# Conversor_R04.net
KiCad netlist of a schematic drawn in EAGLE
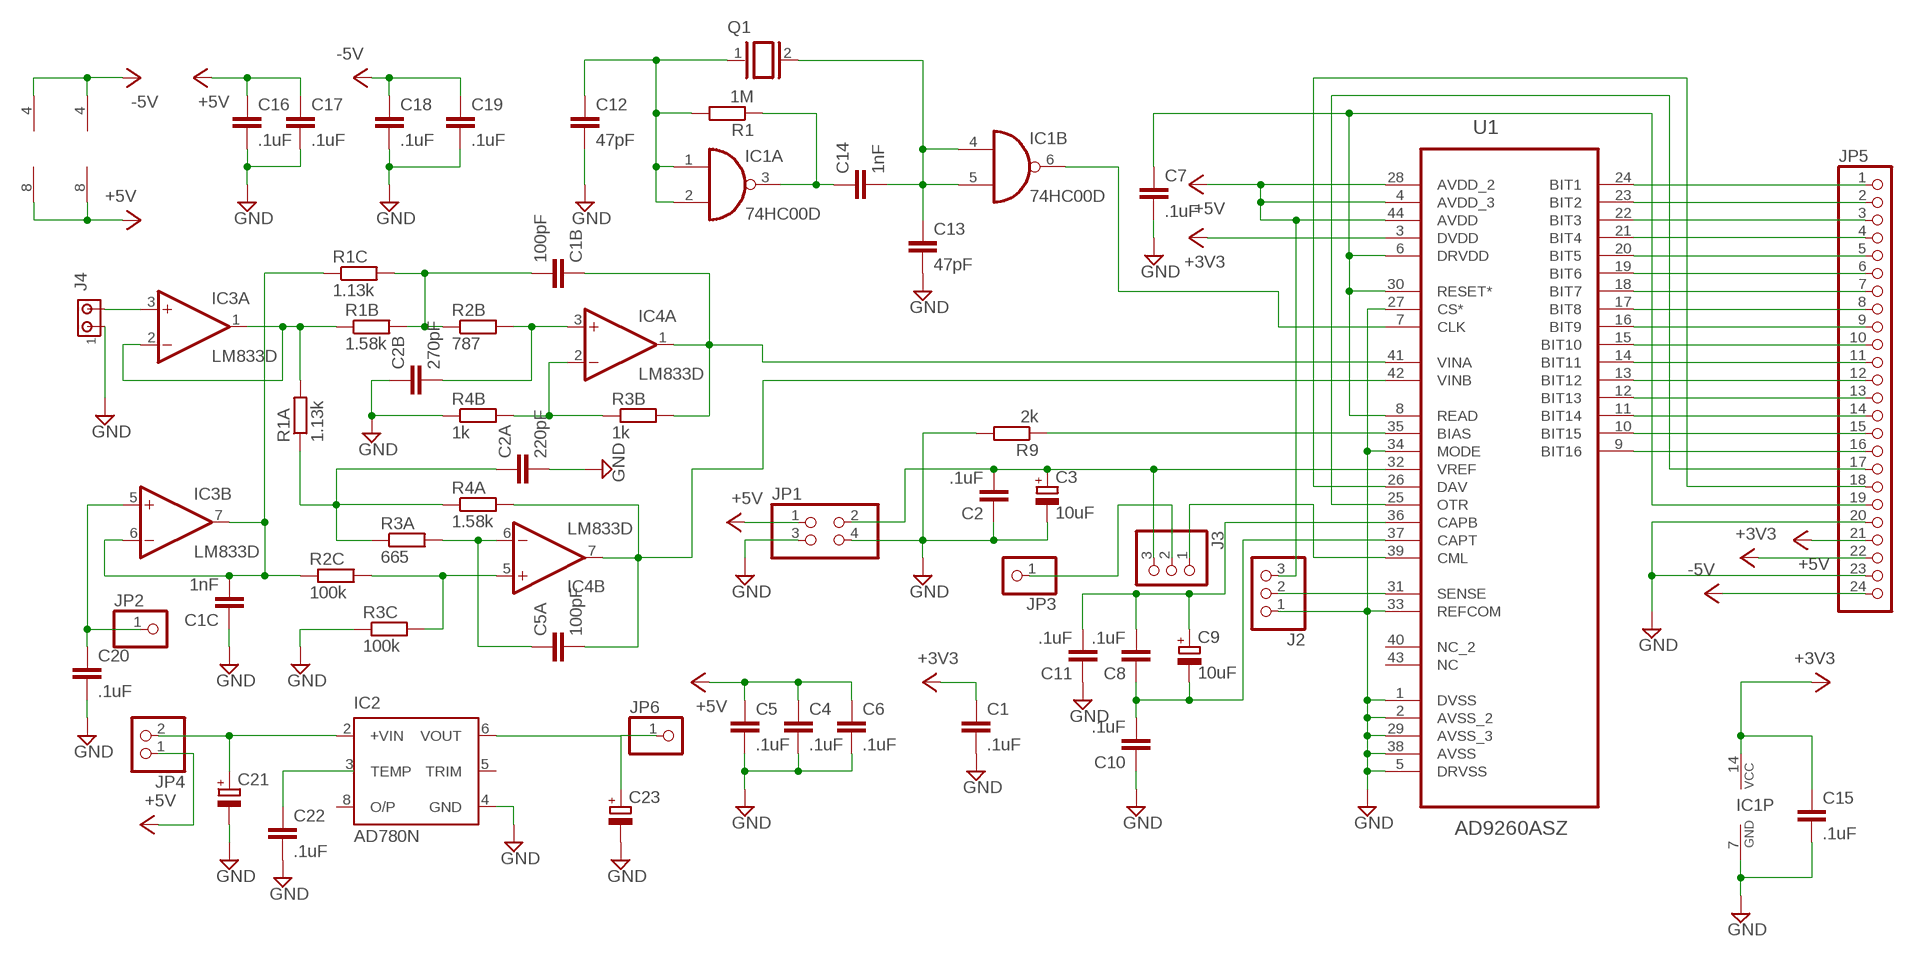
[diagram p0: schematic, sheet 1]

(export (version "E")
  (design (tool "Eeschema 10.0.6"))
  (components
    (comp (ref "C1")
      (value ".1uF")
      (footprint "eagle-import:C050-024X044")
      (libsource (lib "eagle-import") (part "C-EU050-024X044"))
    )
    (comp (ref "C1B")
      (value "100pF")
      (footprint "eagle-import:C025-024X044")
      (libsource (lib "eagle-import") (part "C-EU025-024X044"))
    )
    (comp (ref "C1C")
      (value "1nF")
      (footprint "eagle-import:C025-024X044")
      (libsource (lib "eagle-import") (part "C-EU025-024X044"))
    )
    (comp (ref "C2")
      (value ".1uF")
      (footprint "eagle-import:C050-024X044")
      (libsource (lib "eagle-import") (part "C-EU050-024X044"))
    )
    (comp (ref "C2A")
      (value "220pF")
      (footprint "eagle-import:C050-024X044")
      (libsource (lib "eagle-import") (part "C-EU050-024X044"))
    )
    (comp (ref "C2B")
      (value "270pF")
      (footprint "eagle-import:C025-024X044")
      (libsource (lib "eagle-import") (part "C-EU025-024X044"))
    )
    (comp (ref "C3")
      (value "10uF")
      (footprint "eagle-import:E2-5")
      (libsource (lib "eagle-import") (part "CPOL-EUE2-5"))
    )
    (comp (ref "C4")
      (value ".1uF")
      (footprint "eagle-import:C050-024X044")
      (libsource (lib "eagle-import") (part "C-EU050-024X044"))
    )
    (comp (ref "C5")
      (value ".1uF")
      (footprint "eagle-import:C050-024X044")
      (libsource (lib "eagle-import") (part "C-EU050-024X044"))
    )
    (comp (ref "C5A")
      (value "100pF")
      (footprint "eagle-import:C025-024X044")
      (libsource (lib "eagle-import") (part "C-EU025-024X044"))
    )
    (comp (ref "C6")
      (value ".1uF")
      (footprint "eagle-import:C050-024X044")
      (libsource (lib "eagle-import") (part "C-EU050-024X044"))
    )
    (comp (ref "C7")
      (value ".1uF")
      (footprint "eagle-import:C050-024X044")
      (libsource (lib "eagle-import") (part "C-EU050-024X044"))
    )
    (comp (ref "C8")
      (value ".1uF")
      (footprint "eagle-import:C050-024X044")
      (libsource (lib "eagle-import") (part "C-EU050-024X044"))
    )
    (comp (ref "C9")
      (value "10uF")
      (footprint "eagle-import:E2-5")
      (libsource (lib "eagle-import") (part "CPOL-EUE2-5"))
    )
    (comp (ref "C10")
      (value ".1uF")
      (footprint "eagle-import:C050-024X044")
      (libsource (lib "eagle-import") (part "C-EU050-024X044"))
    )
    (comp (ref "C11")
      (value ".1uF")
      (footprint "eagle-import:C050-024X044")
      (libsource (lib "eagle-import") (part "C-EU050-024X044"))
    )
    (comp (ref "C12")
      (value "47pF")
      (footprint "eagle-import:C025-024X044")
      (libsource (lib "eagle-import") (part "C-EU025-024X044"))
    )
    (comp (ref "C13")
      (value "47pF")
      (footprint "eagle-import:C025-024X044")
      (libsource (lib "eagle-import") (part "C-EU025-024X044"))
    )
    (comp (ref "C14")
      (value "1nF")
      (footprint "eagle-import:C025-024X044")
      (libsource (lib "eagle-import") (part "C-EU025-024X044"))
    )
    (comp (ref "C15")
      (value ".1uF")
      (footprint "eagle-import:C050-024X044")
      (libsource (lib "eagle-import") (part "C-EU050-024X044"))
    )
    (comp (ref "C16")
      (value ".1uF")
      (footprint "eagle-import:C050-024X044")
      (libsource (lib "eagle-import") (part "C-EU050-024X044"))
    )
    (comp (ref "C17")
      (value ".1uF")
      (footprint "eagle-import:C050-024X044")
      (libsource (lib "eagle-import") (part "C-EU050-024X044"))
    )
    (comp (ref "C18")
      (value ".1uF")
      (footprint "eagle-import:C050-024X044")
      (libsource (lib "eagle-import") (part "C-EU050-024X044"))
    )
    (comp (ref "C19")
      (value ".1uF")
      (footprint "eagle-import:C050-024X044")
      (libsource (lib "eagle-import") (part "C-EU050-024X044"))
    )
    (comp (ref "C20")
      (value ".1uF")
      (footprint "eagle-import:C050-024X044")
      (libsource (lib "eagle-import") (part "C-EU050-024X044"))
    )
    (comp (ref "C21")
      (value "CPOL-EUE2,5-6E")
      (footprint "eagle-import:E2,5-6E")
      (libsource (lib "eagle-import") (part "CPOL-EUE2,5-6E"))
    )
    (comp (ref "C22")
      (value ".1uF")
      (footprint "eagle-import:C050-024X044")
      (libsource (lib "eagle-import") (part "C-EU050-024X044"))
    )
    (comp (ref "C23")
      (value "CPOL-EUE2.5-7")
      (footprint "eagle-import:E2,5-7")
      (libsource (lib "eagle-import") (part "CPOL-EUE2.5-7"))
    )
    (comp (ref "IC1")
      (value "74HC00D")
      (footprint "eagle-import:SO14")
      (libsource (lib "eagle-import") (part "7400DHC"))
    )
    (comp (ref "IC2")
      (value "AD780N")
      (footprint "eagle-import:DIL08")
      (fields (field (name "MF") "ALTERA CORPORATION") (field (name "MPN") "AD780ANZ"))
      (libsource (lib "eagle-import") (part "AD780N"))
    )
    (comp (ref "IC3")
      (value "LM833D")
      (footprint "eagle-import:SO08")
      (libsource (lib "eagle-import") (part "LM833D"))
    )
    (comp (ref "IC4")
      (value "LM833D")
      (footprint "eagle-import:SO08")
      (libsource (lib "eagle-import") (part "LM833D"))
    )
    (comp (ref "J2")
      (value "PINHD-1X3")
      (footprint "eagle-import:1X03")
      (libsource (lib "eagle-import") (part "PINHD-1X3"))
    )
    (comp (ref "J3")
      (value "PINHD-1X3")
      (footprint "eagle-import:1X03")
      (libsource (lib "eagle-import") (part "PINHD-1X3"))
    )
    (comp (ref "J4")
      (value "MTA02-156")
      (footprint "eagle-import:1X2MTA")
      (libsource (lib "eagle-import") (part "MTA02-156"))
    )
    (comp (ref "JP1")
      (value "PINHD-2X2")
      (footprint "eagle-import:2X02")
      (libsource (lib "eagle-import") (part "PINHD-2X2"))
    )
    (comp (ref "JP2")
      (value "PINHD-1X1")
      (footprint "eagle-import:1X01")
      (libsource (lib "eagle-import") (part "PINHD-1X1"))
    )
    (comp (ref "JP3")
      (value "PINHD-1X1")
      (footprint "eagle-import:1X01")
      (libsource (lib "eagle-import") (part "PINHD-1X1"))
    )
    (comp (ref "JP4")
      (value "PINHD-1X2")
      (footprint "eagle-import:1X02")
      (libsource (lib "eagle-import") (part "PINHD-1X2"))
    )
    (comp (ref "JP5")
      (value "PINHD-1X24")
      (footprint "eagle-import:1X24")
      (libsource (lib "eagle-import") (part "PINHD-1X24"))
    )
    (comp (ref "JP6")
      (value "PINHD-1X1")
      (footprint "eagle-import:1X01")
      (libsource (lib "eagle-import") (part "PINHD-1X1"))
    )
    (comp (ref "Q1")
      (value "XTAL/S")
      (footprint "eagle-import:QS")
      (libsource (lib "eagle-import") (part "XTAL/S"))
    )
    (comp (ref "R1")
      (value "1M")
      (footprint "eagle-import:0204V")
      (libsource (lib "eagle-import") (part "R-EU_0204/2V"))
    )
    (comp (ref "R1A")
      (value "1.13k")
      (footprint "eagle-import:0204_7")
      (libsource (lib "eagle-import") (part "R-EU_0204/7"))
    )
    (comp (ref "R1B")
      (value "1.58k")
      (footprint "eagle-import:0204V")
      (libsource (lib "eagle-import") (part "R-EU_0204/2V"))
    )
    (comp (ref "R1C")
      (value "1.13k")
      (footprint "eagle-import:0204V")
      (libsource (lib "eagle-import") (part "R-EU_0204/2V"))
    )
    (comp (ref "R2B")
      (value "787")
      (footprint "eagle-import:0204V")
      (libsource (lib "eagle-import") (part "R-EU_0204/2V"))
    )
    (comp (ref "R2C")
      (value "100k")
      (footprint "eagle-import:0204_7")
      (libsource (lib "eagle-import") (part "R-EU_0204/7"))
    )
    (comp (ref "R3A")
      (value "665")
      (footprint "eagle-import:0204_7")
      (libsource (lib "eagle-import") (part "R-EU_0204/7"))
    )
    (comp (ref "R3B")
      (value "1k")
      (footprint "eagle-import:0204V")
      (libsource (lib "eagle-import") (part "R-EU_0204/2V"))
    )
    (comp (ref "R3C")
      (value "100k")
      (footprint "eagle-import:0204_5")
      (libsource (lib "eagle-import") (part "R-EU_0204/5"))
    )
    (comp (ref "R4A")
      (value "1.58k")
      (footprint "eagle-import:0204_7")
      (libsource (lib "eagle-import") (part "R-EU_0204/7"))
    )
    (comp (ref "R4B")
      (value "1k")
      (footprint "eagle-import:0204_7")
      (libsource (lib "eagle-import") (part "R-EU_0204/7"))
    )
    (comp (ref "R9")
      (value "2k")
      (footprint "eagle-import:0204V")
      (libsource (lib "eagle-import") (part "R-EU_0204/2V"))
    )
    (comp (ref "U1")
      (value "AD9260ASZ")
      (footprint "eagle-import:QFP80P1320X1320X245-44N")
      (libsource (lib "eagle-import") (part "AD9260ASZ"))
    )
  )
  (nets
    (net (code "1") (name "+3V3") (class "Default")
      (node (ref "C1") (pin "1") (pinfunction "1_1") (pintype "passive"))
      (node (ref "C15") (pin "1") (pinfunction "1_1") (pintype "passive"))
      (node (ref "IC1") (pin "14") (pinfunction "VCC_14") (pintype "power_in"))
      (node (ref "JP5") (pin "22") (pinfunction "22_22") (pintype "passive"))
      (node (ref "U1") (pin "3") (pinfunction "DVDD_3") (pintype "power_in"))
    )
    (net (code "2") (name "+5V") (class "Default")
      (node (ref "C16") (pin "1") (pinfunction "1_1") (pintype "passive"))
      (node (ref "C17") (pin "1") (pinfunction "1_1") (pintype "passive"))
      (node (ref "C4") (pin "1") (pinfunction "1_1") (pintype "passive"))
      (node (ref "C5") (pin "1") (pinfunction "1_1") (pintype "passive"))
      (node (ref "C6") (pin "1") (pinfunction "1_1") (pintype "passive"))
      (node (ref "IC3") (pin "8") (pinfunction "V+_8") (pintype "power_in"))
      (node (ref "IC4") (pin "8") (pinfunction "V+_8") (pintype "power_in"))
      (node (ref "J2") (pin "3") (pinfunction "3_3") (pintype "passive"))
      (node (ref "JP1") (pin "1") (pinfunction "1_1") (pintype "passive"))
      (node (ref "JP4") (pin "1") (pinfunction "1_1") (pintype "passive"))
      (node (ref "JP5") (pin "21") (pinfunction "21_21") (pintype "passive"))
      (node (ref "U1") (pin "28") (pinfunction "AVDD_2_28") (pintype "power_in"))
      (node (ref "U1") (pin "4") (pinfunction "AVDD_3_4") (pintype "power_in"))
      (node (ref "U1") (pin "44") (pinfunction "AVDD_44") (pintype "power_in"))
    )
    (net (code "3") (name "-5V") (class "Default")
      (node (ref "C18") (pin "1") (pinfunction "1_1") (pintype "passive"))
      (node (ref "C19") (pin "1") (pinfunction "1_1") (pintype "passive"))
      (node (ref "IC3") (pin "4") (pinfunction "V-_4") (pintype "power_in"))
      (node (ref "IC4") (pin "4") (pinfunction "V-_4") (pintype "power_in"))
      (node (ref "JP5") (pin "24") (pinfunction "24_24") (pintype "passive"))
    )
    (net (code "4") (name "GND") (class "Default")
      (node (ref "C1") (pin "2") (pinfunction "2_2") (pintype "passive"))
      (node (ref "C10") (pin "1") (pinfunction "1_1") (pintype "passive"))
      (node (ref "C11") (pin "1") (pinfunction "1_1") (pintype "passive"))
      (node (ref "C12") (pin "2") (pinfunction "2_2") (pintype "passive"))
      (node (ref "C13") (pin "2") (pinfunction "2_2") (pintype "passive"))
      (node (ref "C15") (pin "2") (pinfunction "2_2") (pintype "passive"))
      (node (ref "C16") (pin "2") (pinfunction "2_2") (pintype "passive"))
      (node (ref "C17") (pin "2") (pinfunction "2_2") (pintype "passive"))
      (node (ref "C18") (pin "2") (pinfunction "2_2") (pintype "passive"))
      (node (ref "C19") (pin "2") (pinfunction "2_2") (pintype "passive"))
      (node (ref "C1C") (pin "1") (pinfunction "1_1") (pintype "passive"))
      (node (ref "C2") (pin "1") (pinfunction "1_1") (pintype "passive"))
      (node (ref "C20") (pin "2") (pinfunction "2_2") (pintype "passive"))
      (node (ref "C21") (pin "-") (pinfunction "-_-") (pintype "passive"))
      (node (ref "C22") (pin "2") (pinfunction "2_2") (pintype "passive"))
      (node (ref "C23") (pin "-") (pinfunction "-_-") (pintype "passive"))
      (node (ref "C2A") (pin "2") (pinfunction "2_2") (pintype "passive"))
      (node (ref "C2B") (pin "1") (pinfunction "1_1") (pintype "passive"))
      (node (ref "C3") (pin "-") (pinfunction "-_-") (pintype "passive"))
      (node (ref "C4") (pin "2") (pinfunction "2_2") (pintype "passive"))
      (node (ref "C5") (pin "2") (pinfunction "2_2") (pintype "passive"))
      (node (ref "C6") (pin "2") (pinfunction "2_2") (pintype "passive"))
      (node (ref "C7") (pin "2") (pinfunction "2_2") (pintype "passive"))
      (node (ref "IC1") (pin "7") (pinfunction "GND_7") (pintype "power_in"))
      (node (ref "IC2") (pin "4") (pinfunction "GND_4") (pintype "power_in"))
      (node (ref "J2") (pin "1") (pinfunction "1_1") (pintype "passive"))
      (node (ref "J4") (pin "1") (pinfunction "1_1") (pintype "passive"))
      (node (ref "JP1") (pin "3") (pinfunction "3_3") (pintype "passive"))
      (node (ref "JP1") (pin "4") (pinfunction "4_4") (pintype "passive"))
      (node (ref "JP5") (pin "20") (pinfunction "20_20") (pintype "passive"))
      (node (ref "JP5") (pin "23") (pinfunction "23_23") (pintype "passive"))
      (node (ref "R3C") (pin "1") (pinfunction "1_1") (pintype "passive"))
      (node (ref "R4B") (pin "1") (pinfunction "1_1") (pintype "passive"))
      (node (ref "R9") (pin "2") (pinfunction "2_2") (pintype "passive"))
      (node (ref "U1") (pin "1") (pinfunction "DVSS_1") (pintype "power_in"))
      (node (ref "U1") (pin "2") (pinfunction "AVSS_2_2") (pintype "power_in"))
      (node (ref "U1") (pin "27") (pinfunction "CS*_27") (pintype "passive"))
      (node (ref "U1") (pin "29") (pinfunction "AVSS_3_29") (pintype "power_in"))
      (node (ref "U1") (pin "33") (pinfunction "REFCOM_33") (pintype "passive"))
      (node (ref "U1") (pin "34") (pinfunction "MODE_34") (pintype "passive"))
      (node (ref "U1") (pin "38") (pinfunction "AVSS_38") (pintype "power_in"))
      (node (ref "U1") (pin "5") (pinfunction "DRVSS_5") (pintype "power_in"))
    )
    (net (code "5") (name "Net-(C1B-Pad2)") (class "Default")
      (node (ref "C1B") (pin "2") (pinfunction "2_2") (pintype "passive"))
      (node (ref "R1B") (pin "2") (pinfunction "2_2") (pintype "passive"))
      (node (ref "R1C") (pin "2") (pinfunction "2_2") (pintype "passive"))
      (node (ref "R2B") (pin "1") (pinfunction "1_1") (pintype "passive"))
    )
    (net (code "6") (name "Net-(C2A-Pad1)") (class "Default")
      (node (ref "C2A") (pin "1") (pinfunction "1_1") (pintype "passive"))
      (node (ref "R1A") (pin "1") (pinfunction "1_1") (pintype "passive"))
      (node (ref "R3A") (pin "1") (pinfunction "1_1") (pintype "passive"))
      (node (ref "R4A") (pin "1") (pinfunction "1_1") (pintype "passive"))
    )
    (net (code "7") (name "Net-(IC1A-I0)") (class "Default")
      (node (ref "C12") (pin "1") (pinfunction "1_1") (pintype "passive"))
      (node (ref "IC1") (pin "1") (pinfunction "I0_1") (pintype "input"))
      (node (ref "IC1") (pin "2") (pinfunction "I1_2") (pintype "input"))
      (node (ref "Q1") (pin "1") (pinfunction "1_1") (pintype "passive"))
      (node (ref "R1") (pin "2") (pinfunction "2_2") (pintype "passive"))
    )
    (net (code "8") (name "Net-(IC1A-O)") (class "Default")
      (node (ref "C14") (pin "1") (pinfunction "1_1") (pintype "passive"))
      (node (ref "IC1") (pin "3") (pinfunction "O_3") (pintype "output"))
      (node (ref "R1") (pin "1") (pinfunction "1_1") (pintype "passive"))
    )
    (net (code "9") (name "Net-(IC1B-I0)") (class "Default")
      (node (ref "C13") (pin "1") (pinfunction "1_1") (pintype "passive"))
      (node (ref "C14") (pin "2") (pinfunction "2_2") (pintype "passive"))
      (node (ref "IC1") (pin "4") (pinfunction "I0_4") (pintype "input"))
      (node (ref "IC1") (pin "5") (pinfunction "I1_5") (pintype "input"))
      (node (ref "Q1") (pin "2") (pinfunction "2_2") (pintype "passive"))
    )
    (net (code "10") (name "Net-(IC1B-O)") (class "Default")
      (node (ref "IC1") (pin "6") (pinfunction "O_6") (pintype "output"))
      (node (ref "U1") (pin "7") (pinfunction "CLK_7") (pintype "input"))
    )
    (net (code "11") (name "Net-(IC2-+VIN)") (class "Default")
      (node (ref "C21") (pin "+") (pinfunction "+_+") (pintype "passive"))
      (node (ref "IC2") (pin "2") (pinfunction "+VIN_2") (pintype "input"))
      (node (ref "JP4") (pin "2") (pinfunction "2_2") (pintype "passive"))
    )
    (net (code "12") (name "Net-(IC2-TEMP)") (class "Default")
      (node (ref "C22") (pin "1") (pinfunction "1_1") (pintype "passive"))
      (node (ref "IC2") (pin "3") (pinfunction "TEMP_3") (pintype "input"))
    )
    (net (code "13") (name "Net-(IC2-VOUT)") (class "Default")
      (node (ref "C23") (pin "+") (pinfunction "+_+") (pintype "passive"))
      (node (ref "IC2") (pin "6") (pinfunction "VOUT_6") (pintype "input"))
      (node (ref "JP6") (pin "1") (pinfunction "1_1") (pintype "passive"))
    )
    (net (code "14") (name "Net-(IC3A-+IN)") (class "Default")
      (node (ref "IC3") (pin "3") (pinfunction "+IN_3") (pintype "input"))
      (node (ref "J4") (pin "2") (pinfunction "2_2") (pintype "passive"))
    )
    (net (code "15") (name "Net-(IC3A--IN)") (class "Default")
      (node (ref "IC3") (pin "1") (pinfunction "OUT_1") (pintype "output"))
      (node (ref "IC3") (pin "2") (pinfunction "-IN_2") (pintype "input"))
      (node (ref "R1A") (pin "2") (pinfunction "2_2") (pintype "passive"))
      (node (ref "R1B") (pin "1") (pinfunction "1_1") (pintype "passive"))
    )
    (net (code "16") (name "Net-(IC3B-+IN)") (class "Default")
      (node (ref "C20") (pin "1") (pinfunction "1_1") (pintype "passive"))
      (node (ref "IC3") (pin "5") (pinfunction "+IN_5") (pintype "input"))
      (node (ref "JP2") (pin "1") (pinfunction "1_1") (pintype "passive"))
    )
    (net (code "17") (name "Net-(IC3B--IN)") (class "Default")
      (node (ref "C1C") (pin "2") (pinfunction "2_2") (pintype "passive"))
      (node (ref "IC3") (pin "6") (pinfunction "-IN_6") (pintype "input"))
      (node (ref "IC3") (pin "7") (pinfunction "OUT_7") (pintype "output"))
      (node (ref "R1C") (pin "1") (pinfunction "1_1") (pintype "passive"))
      (node (ref "R2C") (pin "1") (pinfunction "1_1") (pintype "passive"))
    )
    (net (code "18") (name "Net-(IC4A-+IN)") (class "Default")
      (node (ref "C2B") (pin "2") (pinfunction "2_2") (pintype "passive"))
      (node (ref "IC4") (pin "3") (pinfunction "+IN_3") (pintype "input"))
      (node (ref "R2B") (pin "2") (pinfunction "2_2") (pintype "passive"))
    )
    (net (code "19") (name "Net-(IC4A--IN)") (class "Default")
      (node (ref "IC4") (pin "2") (pinfunction "-IN_2") (pintype "input"))
      (node (ref "R3B") (pin "1") (pinfunction "1_1") (pintype "passive"))
      (node (ref "R4B") (pin "2") (pinfunction "2_2") (pintype "passive"))
    )
    (net (code "20") (name "Net-(IC4A-OUT)") (class "Default")
      (node (ref "C1B") (pin "1") (pinfunction "1_1") (pintype "passive"))
      (node (ref "IC4") (pin "1") (pinfunction "OUT_1") (pintype "output"))
      (node (ref "R3B") (pin "2") (pinfunction "2_2") (pintype "passive"))
      (node (ref "U1") (pin "41") (pinfunction "VINA_41") (pintype "input"))
    )
    (net (code "21") (name "Net-(IC4B-+IN)") (class "Default")
      (node (ref "IC4") (pin "5") (pinfunction "+IN_5") (pintype "input"))
      (node (ref "R2C") (pin "2") (pinfunction "2_2") (pintype "passive"))
      (node (ref "R3C") (pin "2") (pinfunction "2_2") (pintype "passive"))
    )
    (net (code "22") (name "Net-(IC4B--IN)") (class "Default")
      (node (ref "C5A") (pin "1") (pinfunction "1_1") (pintype "passive"))
      (node (ref "IC4") (pin "6") (pinfunction "-IN_6") (pintype "input"))
      (node (ref "R3A") (pin "2") (pinfunction "2_2") (pintype "passive"))
    )
    (net (code "23") (name "Net-(IC4B-OUT)") (class "Default")
      (node (ref "C5A") (pin "2") (pinfunction "2_2") (pintype "passive"))
      (node (ref "IC4") (pin "7") (pinfunction "OUT_7") (pintype "output"))
      (node (ref "R4A") (pin "2") (pinfunction "2_2") (pintype "passive"))
      (node (ref "U1") (pin "42") (pinfunction "VINB_42") (pintype "input"))
    )
    (net (code "24") (name "Net-(J3-Pad2)") (class "Default")
      (node (ref "J3") (pin "2") (pinfunction "2_2") (pintype "passive"))
      (node (ref "JP3") (pin "1") (pinfunction "1_1") (pintype "passive"))
    )
    (net (code "25") (name "Net-(U1-BIAS)") (class "Default")
      (node (ref "R9") (pin "1") (pinfunction "1_1") (pintype "passive"))
      (node (ref "U1") (pin "35") (pinfunction "BIAS_35") (pintype "passive"))
    )
    (net (code "26") (name "Net-(U1-BIT1)") (class "Default")
      (node (ref "JP5") (pin "1") (pinfunction "1_1") (pintype "passive"))
      (node (ref "U1") (pin "24") (pinfunction "BIT1_24") (pintype "output"))
    )
    (net (code "27") (name "Net-(U1-BIT2)") (class "Default")
      (node (ref "JP5") (pin "2") (pinfunction "2_2") (pintype "passive"))
      (node (ref "U1") (pin "23") (pinfunction "BIT2_23") (pintype "output"))
    )
    (net (code "28") (name "Net-(U1-BIT3)") (class "Default")
      (node (ref "JP5") (pin "3") (pinfunction "3_3") (pintype "passive"))
      (node (ref "U1") (pin "22") (pinfunction "BIT3_22") (pintype "output"))
    )
    (net (code "29") (name "Net-(U1-BIT4)") (class "Default")
      (node (ref "JP5") (pin "4") (pinfunction "4_4") (pintype "passive"))
      (node (ref "U1") (pin "21") (pinfunction "BIT4_21") (pintype "output"))
    )
    (net (code "30") (name "Net-(U1-BIT5)") (class "Default")
      (node (ref "JP5") (pin "5") (pinfunction "5_5") (pintype "passive"))
      (node (ref "U1") (pin "20") (pinfunction "BIT5_20") (pintype "output"))
    )
    (net (code "31") (name "Net-(U1-BIT6)") (class "Default")
      (node (ref "JP5") (pin "6") (pinfunction "6_6") (pintype "passive"))
      (node (ref "U1") (pin "19") (pinfunction "BIT6_19") (pintype "output"))
    )
    (net (code "32") (name "Net-(U1-BIT7)") (class "Default")
      (node (ref "JP5") (pin "7") (pinfunction "7_7") (pintype "passive"))
      (node (ref "U1") (pin "18") (pinfunction "BIT7_18") (pintype "output"))
    )
    (net (code "33") (name "Net-(U1-BIT8)") (class "Default")
      (node (ref "JP5") (pin "8") (pinfunction "8_8") (pintype "passive"))
      (node (ref "U1") (pin "17") (pinfunction "BIT8_17") (pintype "output"))
    )
    (net (code "34") (name "Net-(U1-BIT9)") (class "Default")
      (node (ref "JP5") (pin "9") (pinfunction "9_9") (pintype "passive"))
      (node (ref "U1") (pin "16") (pinfunction "BIT9_16") (pintype "output"))
    )
    (net (code "35") (name "Net-(U1-BIT10)") (class "Default")
      (node (ref "JP5") (pin "10") (pinfunction "10_10") (pintype "passive"))
      (node (ref "U1") (pin "15") (pinfunction "BIT10_15") (pintype "output"))
    )
    (net (code "36") (name "Net-(U1-BIT11)") (class "Default")
      (node (ref "JP5") (pin "11") (pinfunction "11_11") (pintype "passive"))
      (node (ref "U1") (pin "14") (pinfunction "BIT11_14") (pintype "output"))
    )
    (net (code "37") (name "Net-(U1-BIT12)") (class "Default")
      (node (ref "JP5") (pin "12") (pinfunction "12_12") (pintype "passive"))
      (node (ref "U1") (pin "13") (pinfunction "BIT12_13") (pintype "output"))
    )
    (net (code "38") (name "Net-(U1-BIT13)") (class "Default")
      (node (ref "JP5") (pin "13") (pinfunction "13_13") (pintype "passive"))
      (node (ref "U1") (pin "12") (pinfunction "BIT13_12") (pintype "output"))
    )
    (net (code "39") (name "Net-(U1-BIT14)") (class "Default")
      (node (ref "JP5") (pin "14") (pinfunction "14_14") (pintype "passive"))
      (node (ref "U1") (pin "11") (pinfunction "BIT14_11") (pintype "output"))
    )
    (net (code "40") (name "Net-(U1-BIT15)") (class "Default")
      (node (ref "JP5") (pin "15") (pinfunction "15_15") (pintype "passive"))
      (node (ref "U1") (pin "10") (pinfunction "BIT15_10") (pintype "output"))
    )
    (net (code "41") (name "Net-(U1-BIT16)") (class "Default")
      (node (ref "JP5") (pin "16") (pinfunction "16_16") (pintype "passive"))
      (node (ref "U1") (pin "9") (pinfunction "BIT16_9") (pintype "output"))
    )
    (net (code "42") (name "Net-(U1-CAPB)") (class "Default")
      (node (ref "C11") (pin "2") (pinfunction "2_2") (pintype "passive"))
      (node (ref "C8") (pin "2") (pinfunction "2_2") (pintype "passive"))
      (node (ref "C9") (pin "+") (pinfunction "+_+") (pintype "passive"))
      (node (ref "U1") (pin "36") (pinfunction "CAPB_36") (pintype "passive"))
    )
    (net (code "43") (name "Net-(U1-CAPT)") (class "Default")
      (node (ref "C10") (pin "2") (pinfunction "2_2") (pintype "passive"))
      (node (ref "C8") (pin "1") (pinfunction "1_1") (pintype "passive"))
      (node (ref "C9") (pin "-") (pinfunction "-_-") (pintype "passive"))
      (node (ref "U1") (pin "37") (pinfunction "CAPT_37") (pintype "passive"))
    )
    (net (code "44") (name "Net-(U1-CML)") (class "Default")
      (node (ref "J3") (pin "1") (pinfunction "1_1") (pintype "passive"))
      (node (ref "U1") (pin "39") (pinfunction "CML_39") (pintype "passive"))
    )
    (net (code "45") (name "Net-(U1-DAV)") (class "Default")
      (node (ref "JP5") (pin "18") (pinfunction "18_18") (pintype "passive"))
      (node (ref "U1") (pin "26") (pinfunction "DAV_26") (pintype "passive"))
    )
    (net (code "46") (name "Net-(U1-DRVDD)") (class "Default")
      (node (ref "C7") (pin "1") (pinfunction "1_1") (pintype "passive"))
      (node (ref "JP5") (pin "19") (pinfunction "19_19") (pintype "passive"))
      (node (ref "U1") (pin "30") (pinfunction "RESET*_30") (pintype "passive"))
      (node (ref "U1") (pin "6") (pinfunction "DRVDD_6") (pintype "power_in"))
      (node (ref "U1") (pin "8") (pinfunction "READ_8") (pintype "passive"))
    )
    (net (code "47") (name "Net-(U1-OTR)") (class "Default")
      (node (ref "JP5") (pin "17") (pinfunction "17_17") (pintype "passive"))
      (node (ref "U1") (pin "25") (pinfunction "OTR_25") (pintype "passive"))
    )
    (net (code "48") (name "Net-(U1-SENSE)") (class "Default")
      (node (ref "J2") (pin "2") (pinfunction "2_2") (pintype "passive"))
      (node (ref "U1") (pin "31") (pinfunction "SENSE_31") (pintype "passive"))
    )
    (net (code "49") (name "Net-(U1-VREF)") (class "Default")
      (node (ref "C2") (pin "2") (pinfunction "2_2") (pintype "passive"))
      (node (ref "C3") (pin "+") (pinfunction "+_+") (pintype "passive"))
      (node (ref "J3") (pin "3") (pinfunction "3_3") (pintype "passive"))
      (node (ref "JP1") (pin "2") (pinfunction "2_2") (pintype "passive"))
      (node (ref "U1") (pin "32") (pinfunction "VREF_32") (pintype "input"))
    )
    (net (code "50") (name "unconnected-(IC2-O{slash}P-Pad8)") (class "Default")
      (node (ref "IC2") (pin "8") (pinfunction "O/P_8") (pintype "passive"))
    )
    (net (code "51") (name "unconnected-(IC2-TRIM-Pad5)") (class "Default")
      (node (ref "IC2") (pin "5") (pinfunction "TRIM_5") (pintype "input"))
    )
    (net (code "52") (name "unconnected-(U1-NC-Pad43)") (class "Default")
      (node (ref "U1") (pin "43") (pinfunction "NC_43") (pintype "no_connect"))
    )
    (net (code "53") (name "unconnected-(U1-NC_2-Pad40)") (class "Default")
      (node (ref "U1") (pin "40") (pinfunction "NC_2_40") (pintype "no_connect"))
    )
  )
)
